# Power_Supply.net
KiCad netlist of a schematic drawn in Altium Designer
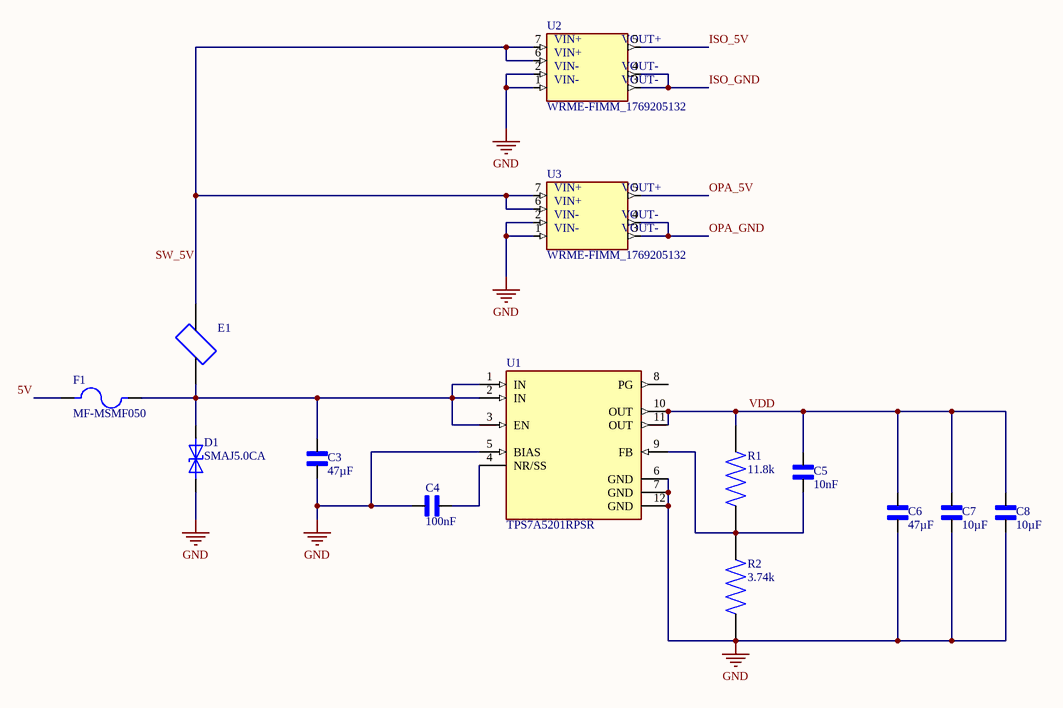
[diagram p0: Power Supply.SchDoc]

(export (version "E")
  (design (tool "Eeschema 10.0.6"))
  (components
    (comp (ref "C3")
      (value "47µF")
      (footprint "CAPC3225X270N")
      (description "47 ÂµF Â±10% 10V Ceramic Capacitor X7R 1210 (3225 Metric)")
      (fields (field (name "MP") "CL32B476KPJNNWE") (field (name "MF") "Samsung"))
      (libsource (lib "James' Workspace") (part "CL32B476KPJNNWE"))
    )
    (comp (ref "C4")
      (value "100nF")
      (footprint "CAPC2012X88N")
      (description "0.1 ÂµF Â±10% 35V Ceramic Capacitor X7R 0805 (2012 Metric)")
      (fields (field (name "MP") "C0805C104K6RACTU") (field (name "MF") "KEMET"))
      (libsource (lib "James' Workspace") (part "C0805C104K6RACTU"))
    )
    (comp (ref "C5")
      (value "10nF")
      (footprint "CAPC2012X88N")
      (description "Capacitor;Ceramic;Cap 0.01uF;Tol 5%;Vol-Rtg 50 V;SMT;Case 0805;X7R;TR")
      (fields (field (name "MP") "C0805C103J5RACTU") (field (name "MF") "KEMET"))
      (libsource (lib "James' Workspace") (part "C0805C103J5RACTU"))
    )
    (comp (ref "C6")
      (value "47µF")
      (footprint "CAPC3225X270N")
      (description "47 ÂµF Â±10% 10V Ceramic Capacitor X7R 1210 (3225 Metric)")
      (fields (field (name "MP") "CL32B476KPJNNWE") (field (name "MF") "Samsung"))
      (libsource (lib "James' Workspace") (part "CL32B476KPJNNWE"))
    )
    (comp (ref "C7")
      (value "10µF")
      (footprint "CAPC3225X280N")
      (description "10 ÂµF Â±10% 50V Ceramic Capacitor X5R 1210 (3225 Metric)")
      (fields (field (name "MP") "C1210C106K5PACTU") (field (name "MF") "KEMET"))
      (libsource (lib "James' Workspace") (part "C1210C106K5PACTU"))
    )
    (comp (ref "C8")
      (value "10µF")
      (footprint "CAPC3225X280N")
      (description "10 ÂµF Â±10% 50V Ceramic Capacitor X5R 1210 (3225 Metric)")
      (fields (field (name "MP") "C1210C106K5PACTU") (field (name "MF") "KEMET"))
      (libsource (lib "James' Workspace") (part "C1210C106K5PACTU"))
    )
    (comp (ref "D1")
      (value "SMAJ5.0CA")
      (footprint "DIOM5126X229N")
      (description "A 5.0V, 400W, bi-directional, SMA pkg TVS Diode")
      (fields (field (name "MF") "Bourns"))
      (libsource (lib "James' Workspace") (part "SMAJ5.0CA"))
    )
    (comp (ref "E1")
      (value "2-2176744-2")
      (footprint "BEADC2012X110N")
      (description "600 Ohms @ 100 MHz 1 Power Line Ferrite Bead 0805 (2012 Metric) 1.5A 250mOhm")
      (fields (field (name "MF") "TE Connectivity Passive Product"))
      (libsource (lib "James' Workspace") (part "2-2176744-2"))
    )
    (comp (ref "F1")
      (value "MF-MSMF050")
      (footprint "FUSER_MF-MSMF050")
      (description "Polymeric PTC Resettable Fuse 40V 500 mA Ih Surface Mount 1812 (4532 Metric), Concave")
      (fields (field (name "MF") "Bourns"))
      (libsource (lib "James' Workspace") (part "MF-MSMF050"))
    )
    (comp (ref "R1")
      (value "11.8k")
      (footprint "RESC2012X50N")
      (description "Res Thick Film 0805 11.8K Ohm 1% 0.125W(1/8W) Â±100ppm/C Molded SMD Automotive Paper T/R")
      (fields (field (name "MF") "Vishay") (field (name "MP") "CRCW080511K8FKEC"))
      (libsource (lib "James' Workspace") (part "CRCW080511K8FKEC"))
    )
    (comp (ref "R2")
      (value "3.74k")
      (footprint "RESC2012X50N")
      (description "Resistor;Thick Film;3.74 Kilohms;0.125 W;1%;SMT;0805;TCR 37 ppm/DegC;TR")
      (fields (field (name "MF") "Vishay Dale") (field (name "MP") "CRCW08053K74FKEA"))
      (libsource (lib "James' Workspace") (part "CRCW08053K74FKEA"))
    )
    (comp (ref "U1")
      (value "TPS7A5201RPSR")
      (footprint "IC_TPS7A5201RPSR")
      (description "LDO")
      (fields (field (name "MF") "{'manufacturer': u'Texas Instruments'}"))
      (libsource (lib "James' Workspace") (part "TPS7A5201RPSR"))
    )
    (comp (ref "U2")
      (value "WRME-FIMM_1769205132")
      (footprint "WRME-FIMM_1769205132")
      (description "LGA-7 / 5Vin / 5Vout / 1W / 3kV / 9 x 7 x 3.1mm / short circuit protection")
      (fields (field (name "MP") "1769205132") (field (name "MF") "Wurth Elektronik"))
      (libsource (lib "James' Workspace") (part "WRME-FIMM_1769205132"))
    )
    (comp (ref "U3")
      (value "WRME-FIMM_1769205132")
      (footprint "WRME-FIMM_1769205132")
      (description "LGA-7 / 5Vin / 5Vout / 1W / 3kV / 9 x 7 x 3.1mm / short circuit protection")
      (fields (field (name "MP") "1769205132") (field (name "MF") "Wurth Elektronik"))
      (libsource (lib "James' Workspace") (part "WRME-FIMM_1769205132"))
    )
  )
  (nets
    (net (code "1") (name "/5V") (class "Default")
      (node (ref "F1") (pin "1") (pinfunction "1_1") (pintype "passive"))
    )
    (net (code "2") (name "/ISO_5V") (class "Default")
      (node (ref "U2") (pin "5") (pinfunction "5_5") (pintype "output"))
    )
    (net (code "3") (name "/ISO_GND") (class "Default")
      (node (ref "U2") (pin "3") (pinfunction "3_3") (pintype "output"))
      (node (ref "U2") (pin "4") (pinfunction "4_4") (pintype "output"))
    )
    (net (code "4") (name "/OPA_5V") (class "Default")
      (node (ref "U3") (pin "5") (pinfunction "5_5") (pintype "output"))
    )
    (net (code "5") (name "/OPA_GND") (class "Default")
      (node (ref "U3") (pin "3") (pinfunction "3_3") (pintype "output"))
      (node (ref "U3") (pin "4") (pinfunction "4_4") (pintype "output"))
    )
    (net (code "6") (name "/SW_5V") (class "Default")
      (node (ref "E1") (pin "2") (pinfunction "2_2") (pintype "passive"))
      (node (ref "U2") (pin "6") (pinfunction "6_6") (pintype "input"))
      (node (ref "U2") (pin "7") (pinfunction "7_7") (pintype "input"))
      (node (ref "U3") (pin "6") (pinfunction "6_6") (pintype "input"))
      (node (ref "U3") (pin "7") (pinfunction "7_7") (pintype "input"))
    )
    (net (code "7") (name "/VDD") (class "Default")
      (node (ref "C5") (pin "2") (pinfunction "2_2") (pintype "passive"))
      (node (ref "C6") (pin "1") (pinfunction "1_1") (pintype "passive"))
      (node (ref "C7") (pin "1") (pinfunction "1_1") (pintype "passive"))
      (node (ref "C8") (pin "1") (pinfunction "1_1") (pintype "passive"))
      (node (ref "R1") (pin "1") (pinfunction "1_1") (pintype "passive"))
      (node (ref "U1") (pin "10") (pinfunction "OUT_10") (pintype "output"))
      (node (ref "U1") (pin "11") (pinfunction "OUT_11") (pintype "output"))
    )
    (net (code "8") (name "GND") (class "Default")
      (node (ref "C3") (pin "2") (pinfunction "2_2") (pintype "passive"))
      (node (ref "C4") (pin "2") (pinfunction "2_2") (pintype "passive"))
      (node (ref "C6") (pin "2") (pinfunction "2_2") (pintype "passive"))
      (node (ref "C7") (pin "2") (pinfunction "2_2") (pintype "passive"))
      (node (ref "C8") (pin "2") (pinfunction "2_2") (pintype "passive"))
      (node (ref "D1") (pin "2") (pinfunction "2_2") (pintype "passive"))
      (node (ref "R2") (pin "2") (pinfunction "2_2") (pintype "passive"))
      (node (ref "U1") (pin "12") (pinfunction "GND_12") (pintype "power_in"))
      (node (ref "U1") (pin "5") (pinfunction "BIAS_5") (pintype "input"))
      (node (ref "U1") (pin "6") (pinfunction "GND_6") (pintype "power_in"))
      (node (ref "U1") (pin "7") (pinfunction "GND_7") (pintype "power_in"))
      (node (ref "U2") (pin "1") (pinfunction "1_1") (pintype "input"))
      (node (ref "U2") (pin "2") (pinfunction "2_2") (pintype "input"))
      (node (ref "U3") (pin "1") (pinfunction "1_1") (pintype "input"))
      (node (ref "U3") (pin "2") (pinfunction "2_2") (pintype "input"))
    )
    (net (code "9") (name "Net-(U1-EN)") (class "Default")
      (node (ref "C3") (pin "1") (pinfunction "1_1") (pintype "passive"))
      (node (ref "D1") (pin "1") (pinfunction "1_1") (pintype "passive"))
      (node (ref "E1") (pin "1") (pinfunction "1_1") (pintype "passive"))
      (node (ref "F1") (pin "2") (pinfunction "2_2") (pintype "passive"))
      (node (ref "U1") (pin "1") (pinfunction "IN_1") (pintype "input"))
      (node (ref "U1") (pin "2") (pinfunction "IN_2") (pintype "input"))
      (node (ref "U1") (pin "3") (pinfunction "EN_3") (pintype "input"))
    )
    (net (code "10") (name "Net-(U1-FB)") (class "Default")
      (node (ref "C5") (pin "1") (pinfunction "1_1") (pintype "passive"))
      (node (ref "R1") (pin "2") (pinfunction "2_2") (pintype "passive"))
      (node (ref "R2") (pin "1") (pinfunction "1_1") (pintype "passive"))
      (node (ref "U1") (pin "9") (pinfunction "FB_9") (pintype "input"))
    )
    (net (code "11") (name "Net-(U1-NR{slash}SS)") (class "Default")
      (node (ref "C4") (pin "1") (pinfunction "1_1") (pintype "passive"))
      (node (ref "U1") (pin "4") (pinfunction "NR/SS_4") (pintype "passive"))
    )
    (net (code "12") (name "unconnected-(U1-PG-Pad8)") (class "Default")
      (node (ref "U1") (pin "8") (pinfunction "PG_8") (pintype "output"))
    )
  )
)
